# 09-I225-2.net
KiCad netlist of a schematic drawn in Altium Designer
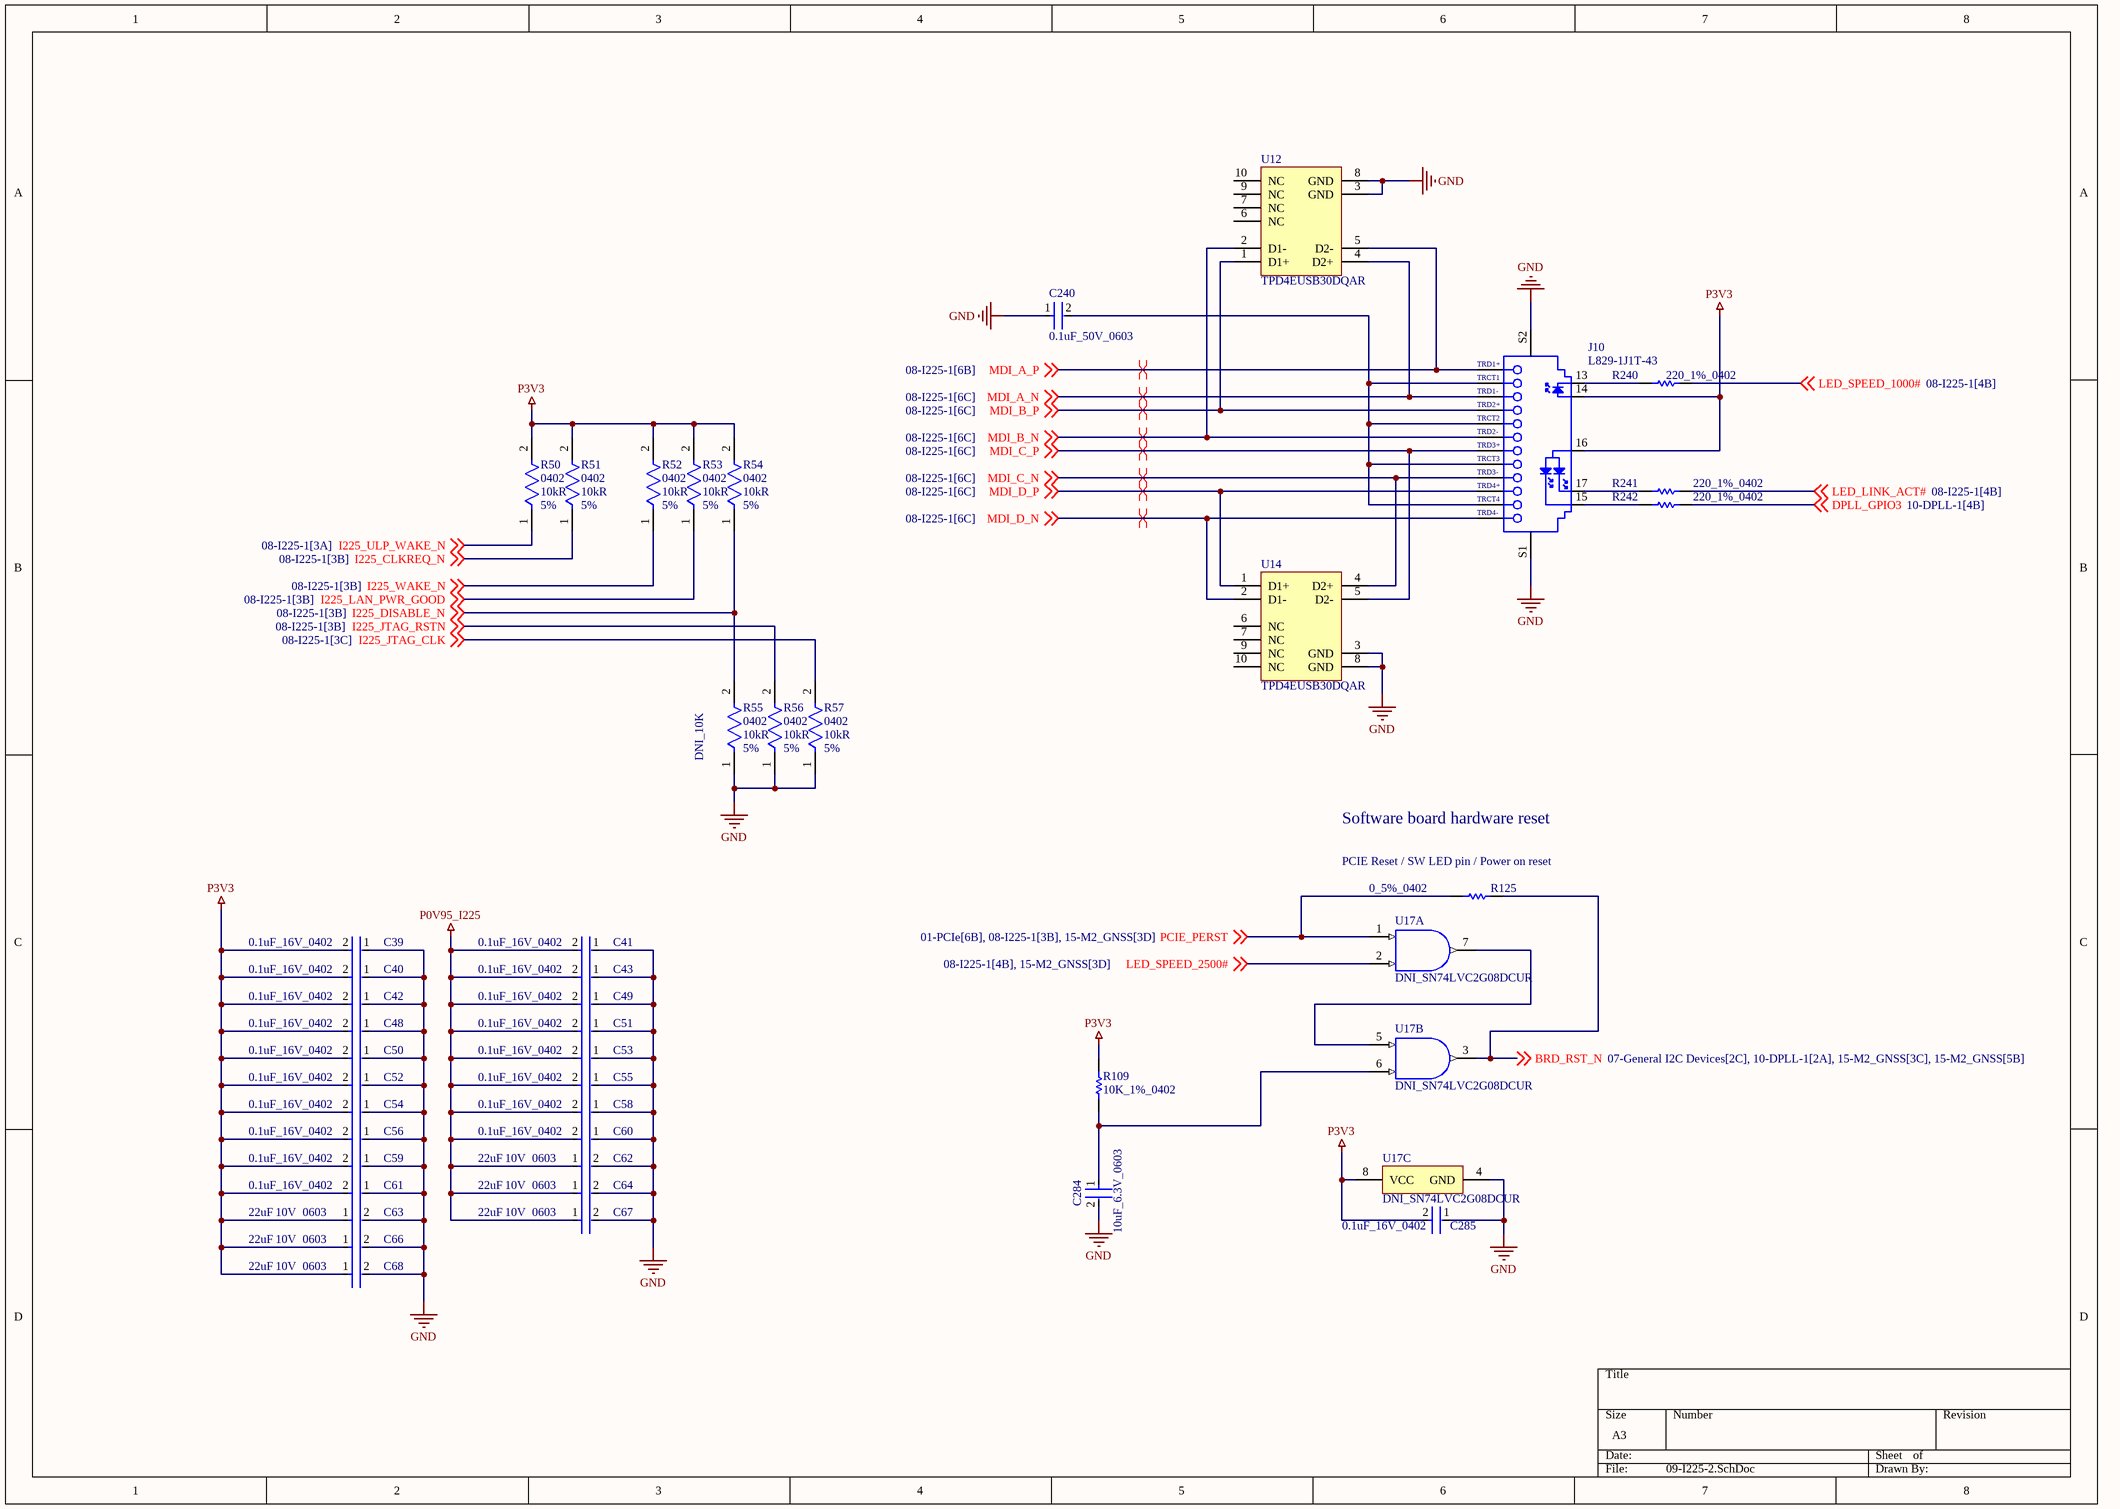
[diagram p0: 09-I225-2.SchDoc]

(export (version "E")
  (design (tool "Eeschema 10.0.6"))
  (components
    (comp (ref "C39")
      (value "0.1uF_16V_0402")
      (footprint "FP-GRM15-MFG")
      (description "CAP CER 0.1UF 16V X7R 0402")
      (fields (field (name "MANUFACTURER PART NUMBER") "GRM155R71C104KA88D") (field (name "TOLERANCE") "10%"))
      (libsource (lib "Altium Content Vault") (part "236180d848d6139a670b325ea6854c9"))
    )
    (comp (ref "C40")
      (value "0.1uF_16V_0402")
      (footprint "FP-GRM15-MFG")
      (description "CAP CER 0.1UF 16V X7R 0402")
      (fields (field (name "MANUFACTURER PART NUMBER") "GRM155R71C104KA88D") (field (name "TOLERANCE") "10%"))
      (libsource (lib "Altium Content Vault") (part "236180d848d6139a670b325ea6854c9"))
    )
    (comp (ref "C41")
      (value "0.1uF_16V_0402")
      (footprint "FP-GRM15-MFG")
      (description "CAP CER 0.1UF 16V X7R 0402")
      (fields (field (name "MANUFACTURER PART NUMBER") "GRM155R71C104KA88D") (field (name "TOLERANCE") "10%"))
      (libsource (lib "Altium Content Vault") (part "236180d848d6139a670b325ea6854c9"))
    )
    (comp (ref "C42")
      (value "0.1uF_16V_0402")
      (footprint "FP-GRM15-MFG")
      (description "CAP CER 0.1UF 16V X7R 0402")
      (fields (field (name "MANUFACTURER PART NUMBER") "GRM155R71C104KA88D") (field (name "TOLERANCE") "10%"))
      (libsource (lib "Altium Content Vault") (part "236180d848d6139a670b325ea6854c9"))
    )
    (comp (ref "C43")
      (value "0.1uF_16V_0402")
      (footprint "FP-GRM15-MFG")
      (description "CAP CER 0.1UF 16V X7R 0402")
      (fields (field (name "MANUFACTURER PART NUMBER") "GRM155R71C104KA88D") (field (name "TOLERANCE") "10%"))
      (libsource (lib "Altium Content Vault") (part "236180d848d6139a670b325ea6854c9"))
    )
    (comp (ref "C48")
      (value "0.1uF_16V_0402")
      (footprint "FP-GRM15-MFG")
      (description "CAP CER 0.1UF 16V X7R 0402")
      (fields (field (name "MANUFACTURER PART NUMBER") "GRM155R71C104KA88D") (field (name "TOLERANCE") "10%"))
      (libsource (lib "Altium Content Vault") (part "236180d848d6139a670b325ea6854c9"))
    )
    (comp (ref "C49")
      (value "0.1uF_16V_0402")
      (footprint "FP-GRM15-MFG")
      (description "CAP CER 0.1UF 16V X7R 0402")
      (fields (field (name "MANUFACTURER PART NUMBER") "GRM155R71C104KA88D") (field (name "TOLERANCE") "10%"))
      (libsource (lib "Altium Content Vault") (part "236180d848d6139a670b325ea6854c9"))
    )
    (comp (ref "C50")
      (value "0.1uF_16V_0402")
      (footprint "FP-GRM15-MFG")
      (description "CAP CER 0.1UF 16V X7R 0402")
      (fields (field (name "MANUFACTURER PART NUMBER") "GRM155R71C104KA88D") (field (name "TOLERANCE") "10%"))
      (libsource (lib "Altium Content Vault") (part "236180d848d6139a670b325ea6854c9"))
    )
    (comp (ref "C51")
      (value "0.1uF_16V_0402")
      (footprint "FP-GRM15-MFG")
      (description "CAP CER 0.1UF 16V X7R 0402")
      (fields (field (name "MANUFACTURER PART NUMBER") "GRM155R71C104KA88D") (field (name "TOLERANCE") "10%"))
      (libsource (lib "Altium Content Vault") (part "236180d848d6139a670b325ea6854c9"))
    )
    (comp (ref "C52")
      (value "0.1uF_16V_0402")
      (footprint "FP-GRM15-MFG")
      (description "CAP CER 0.1UF 16V X7R 0402")
      (fields (field (name "MANUFACTURER PART NUMBER") "GRM155R71C104KA88D") (field (name "TOLERANCE") "10%"))
      (libsource (lib "Altium Content Vault") (part "236180d848d6139a670b325ea6854c9"))
    )
    (comp (ref "C53")
      (value "0.1uF_16V_0402")
      (footprint "FP-GRM15-MFG")
      (description "CAP CER 0.1UF 16V X7R 0402")
      (fields (field (name "MANUFACTURER PART NUMBER") "GRM155R71C104KA88D") (field (name "TOLERANCE") "10%"))
      (libsource (lib "Altium Content Vault") (part "236180d848d6139a670b325ea6854c9"))
    )
    (comp (ref "C54")
      (value "0.1uF_16V_0402")
      (footprint "FP-GRM15-MFG")
      (description "CAP CER 0.1UF 16V X7R 0402")
      (fields (field (name "MANUFACTURER PART NUMBER") "GRM155R71C104KA88D") (field (name "TOLERANCE") "10%"))
      (libsource (lib "Altium Content Vault") (part "236180d848d6139a670b325ea6854c9"))
    )
    (comp (ref "C55")
      (value "0.1uF_16V_0402")
      (footprint "FP-GRM15-MFG")
      (description "CAP CER 0.1UF 16V X7R 0402")
      (fields (field (name "MANUFACTURER PART NUMBER") "GRM155R71C104KA88D") (field (name "TOLERANCE") "10%"))
      (libsource (lib "Altium Content Vault") (part "236180d848d6139a670b325ea6854c9"))
    )
    (comp (ref "C56")
      (value "0.1uF_16V_0402")
      (footprint "FP-GRM15-MFG")
      (description "CAP CER 0.1UF 16V X7R 0402")
      (fields (field (name "MANUFACTURER PART NUMBER") "GRM155R71C104KA88D") (field (name "TOLERANCE") "10%"))
      (libsource (lib "Altium Content Vault") (part "236180d848d6139a670b325ea6854c9"))
    )
    (comp (ref "C58")
      (value "0.1uF_16V_0402")
      (footprint "FP-GRM15-MFG")
      (description "CAP CER 0.1UF 16V X7R 0402")
      (fields (field (name "MANUFACTURER PART NUMBER") "GRM155R71C104KA88D") (field (name "TOLERANCE") "10%"))
      (libsource (lib "Altium Content Vault") (part "236180d848d6139a670b325ea6854c9"))
    )
    (comp (ref "C59")
      (value "0.1uF_16V_0402")
      (footprint "FP-GRM15-MFG")
      (description "CAP CER 0.1UF 16V X7R 0402")
      (fields (field (name "MANUFACTURER PART NUMBER") "GRM155R71C104KA88D") (field (name "TOLERANCE") "10%"))
      (libsource (lib "Altium Content Vault") (part "236180d848d6139a670b325ea6854c9"))
    )
    (comp (ref "C60")
      (value "0.1uF_16V_0402")
      (footprint "FP-GRM15-MFG")
      (description "CAP CER 0.1UF 16V X7R 0402")
      (fields (field (name "MANUFACTURER PART NUMBER") "GRM155R71C104KA88D") (field (name "TOLERANCE") "10%"))
      (libsource (lib "Altium Content Vault") (part "236180d848d6139a670b325ea6854c9"))
    )
    (comp (ref "C61")
      (value "0.1uF_16V_0402")
      (footprint "FP-GRM15-MFG")
      (description "CAP CER 0.1UF 16V X7R 0402")
      (fields (field (name "MANUFACTURER PART NUMBER") "GRM155R71C104KA88D") (field (name "TOLERANCE") "10%"))
      (libsource (lib "Altium Content Vault") (part "236180d848d6139a670b325ea6854c9"))
    )
    (comp (ref "C62")
      (value "GRM188R61A226ME15D")
      (footprint "FP-GRM188-0_2-IPC_C")
      (description "Chip Multilayer Ceramic Capacitors for General Purpose, 0603, 22uF, X5R, 15%, 20%, 10V")
      (fields
        (field (name "TOLERANCE") "20%")
        (field (name "CAPACITANCE") "22uF")
        (field (name "VOLTAGE RATING") "10V")
        (field (name "CASE CODE (IMPERIAL)") "0603")
      )
      (libsource (lib "Altium Content Vault") (part "11868f565c42a9108669ba33697ecf6"))
    )
    (comp (ref "C63")
      (value "GRM188R61A226ME15D")
      (footprint "FP-GRM188-0_2-IPC_C")
      (description "Chip Multilayer Ceramic Capacitors for General Purpose, 0603, 22uF, X5R, 15%, 20%, 10V")
      (fields
        (field (name "TOLERANCE") "20%")
        (field (name "CAPACITANCE") "22uF")
        (field (name "VOLTAGE RATING") "10V")
        (field (name "CASE CODE (IMPERIAL)") "0603")
      )
      (libsource (lib "Altium Content Vault") (part "11868f565c42a9108669ba33697ecf6"))
    )
    (comp (ref "C64")
      (value "GRM188R61A226ME15D")
      (footprint "FP-GRM188-0_2-IPC_C")
      (description "Chip Multilayer Ceramic Capacitors for General Purpose, 0603, 22uF, X5R, 15%, 20%, 10V")
      (fields
        (field (name "TOLERANCE") "20%")
        (field (name "CAPACITANCE") "22uF")
        (field (name "VOLTAGE RATING") "10V")
        (field (name "CASE CODE (IMPERIAL)") "0603")
      )
      (libsource (lib "Altium Content Vault") (part "11868f565c42a9108669ba33697ecf6"))
    )
    (comp (ref "C66")
      (value "GRM188R61A226ME15D")
      (footprint "FP-GRM188-0_2-IPC_C")
      (description "Chip Multilayer Ceramic Capacitors for General Purpose, 0603, 22uF, X5R, 15%, 20%, 10V")
      (fields
        (field (name "TOLERANCE") "20%")
        (field (name "CAPACITANCE") "22uF")
        (field (name "VOLTAGE RATING") "10V")
        (field (name "CASE CODE (IMPERIAL)") "0603")
      )
      (libsource (lib "Altium Content Vault") (part "11868f565c42a9108669ba33697ecf6"))
    )
    (comp (ref "C67")
      (value "GRM188R61A226ME15D")
      (footprint "FP-GRM188-0_2-IPC_C")
      (description "Chip Multilayer Ceramic Capacitors for General Purpose, 0603, 22uF, X5R, 15%, 20%, 10V")
      (fields
        (field (name "TOLERANCE") "20%")
        (field (name "CAPACITANCE") "22uF")
        (field (name "VOLTAGE RATING") "10V")
        (field (name "CASE CODE (IMPERIAL)") "0603")
      )
      (libsource (lib "Altium Content Vault") (part "11868f565c42a9108669ba33697ecf6"))
    )
    (comp (ref "C68")
      (value "GRM188R61A226ME15D")
      (footprint "FP-GRM188-0_2-IPC_C")
      (description "Chip Multilayer Ceramic Capacitors for General Purpose, 0603, 22uF, X5R, 15%, 20%, 10V")
      (fields
        (field (name "TOLERANCE") "20%")
        (field (name "CAPACITANCE") "22uF")
        (field (name "VOLTAGE RATING") "10V")
        (field (name "CASE CODE (IMPERIAL)") "0603")
      )
      (libsource (lib "Altium Content Vault") (part "11868f565c42a9108669ba33697ecf6"))
    )
    (comp (ref "C240")
      (value "0.1uF_50V_0603")
      (footprint "FP-C0603-CJ-MFG")
      (description "CAP CER 0.1UF 50V X7R 0603")
      (fields (field (name "MANUFACTURER PART NUMBER") "C0603X104K5RACTU") (field (name "VOLTAGE") "50V"))
      (libsource (lib "Altium Content Vault") (part "11868f565c42a9108669ba33697ecf6"))
    )
    (comp (ref "C284")
      (value "10uF_6.3V_0603")
      (footprint "FP-C0603C106M9PACTU-MFG")
      (description "CAP CER 10UF 6.3V X5R 0603")
      (fields
        (field (name "MANUFACTURER PART NUMBER") "C0603C106M9PACTU")
        (field (name "MANUFACTURER") "Kemet")
      )
      (libsource (lib "Altium Content Vault") (part "b4654b650e69147ec39a6b967a45e02"))
    )
    (comp (ref "C285")
      (value "0.1uF_16V_0402")
      (footprint "FP-GRM15-MFG")
      (description "CAP CER 0.1UF 16V X7R 0402")
      (fields (field (name "MANUFACTURER PART NUMBER") "GRM155R71C104KA88D") (field (name "TOLERANCE") "10%"))
      (libsource (lib "Altium Content Vault") (part "236180d848d6139a670b325ea6854c9"))
    )
    (comp (ref "J10")
      (value "L829-1J1T-43")
      (footprint "BELS-L829-1J1T-43_V")
      (description "Gigabit MagJack(R) Ultra Low Profile, 10/100/1000 Base-T, 19-Pin THD, RoHS, Tray")
      (libsource (lib "Altium Content Vault") (part "RJ45-17-2SHLD"))
    )
    (comp (ref "R50")
      (value "CRCW040210K0JNED")
      (footprint "FP-CRCW0402-e3-IPC_B")
      (description "RES Thick Film, 10kΩ, 5%, 0.063W, 200ppm/°C, 0402")
      (fields
        (field (name "CASE/PACKAGE") "0402")
        (field (name "RESISTANCE") "10kR")
        (field (name "TOLERANCE") "5%")
      )
      (libsource (lib "Altium Content Vault") (part "1029c3af85768c4190bb7ad29bc67b5"))
    )
    (comp (ref "R51")
      (value "CRCW040210K0JNED")
      (footprint "FP-CRCW0402-e3-IPC_B")
      (description "RES Thick Film, 10kΩ, 5%, 0.063W, 200ppm/°C, 0402")
      (fields
        (field (name "CASE/PACKAGE") "0402")
        (field (name "RESISTANCE") "10kR")
        (field (name "TOLERANCE") "5%")
      )
      (libsource (lib "Altium Content Vault") (part "1029c3af85768c4190bb7ad29bc67b5"))
    )
    (comp (ref "R52")
      (value "CRCW040210K0JNED")
      (footprint "FP-CRCW0402-e3-IPC_B")
      (description "RES Thick Film, 10kΩ, 5%, 0.063W, 200ppm/°C, 0402")
      (fields
        (field (name "CASE/PACKAGE") "0402")
        (field (name "RESISTANCE") "10kR")
        (field (name "TOLERANCE") "5%")
      )
      (libsource (lib "Altium Content Vault") (part "1029c3af85768c4190bb7ad29bc67b5"))
    )
    (comp (ref "R53")
      (value "CRCW040210K0JNED")
      (footprint "FP-CRCW0402-e3-IPC_B")
      (description "RES Thick Film, 10kΩ, 5%, 0.063W, 200ppm/°C, 0402")
      (fields
        (field (name "CASE/PACKAGE") "0402")
        (field (name "RESISTANCE") "10kR")
        (field (name "TOLERANCE") "5%")
      )
      (libsource (lib "Altium Content Vault") (part "1029c3af85768c4190bb7ad29bc67b5"))
    )
    (comp (ref "R54")
      (value "CRCW040210K0JNED")
      (footprint "FP-CRCW0402-e3-IPC_B")
      (description "RES Thick Film, 10kΩ, 5%, 0.063W, 200ppm/°C, 0402")
      (fields
        (field (name "CASE/PACKAGE") "0402")
        (field (name "RESISTANCE") "10kR")
        (field (name "TOLERANCE") "5%")
      )
      (libsource (lib "Altium Content Vault") (part "1029c3af85768c4190bb7ad29bc67b5"))
    )
    (comp (ref "R55")
      (value "DNI_10K")
      (footprint "FP-CRCW0402-e3-IPC_B")
      (description "RES Thick Film, 10kΩ, 5%, 0.063W, 200ppm/°C, 0402")
      (fields
        (field (name "CASE/PACKAGE") "0402")
        (field (name "RESISTANCE") "10kR")
        (field (name "TOLERANCE") "5%")
      )
      (libsource (lib "Altium Content Vault") (part "1029c3af85768c4190bb7ad29bc67b5"))
    )
    (comp (ref "R56")
      (value "CRCW040210K0JNED")
      (footprint "FP-CRCW0402-e3-IPC_B")
      (description "RES Thick Film, 10kΩ, 5%, 0.063W, 200ppm/°C, 0402")
      (fields
        (field (name "CASE/PACKAGE") "0402")
        (field (name "RESISTANCE") "10kR")
        (field (name "TOLERANCE") "5%")
      )
      (libsource (lib "Altium Content Vault") (part "1029c3af85768c4190bb7ad29bc67b5"))
    )
    (comp (ref "R57")
      (value "CRCW040210K0JNED")
      (footprint "FP-CRCW0402-e3-IPC_B")
      (description "RES Thick Film, 10kΩ, 5%, 0.063W, 200ppm/°C, 0402")
      (fields
        (field (name "CASE/PACKAGE") "0402")
        (field (name "RESISTANCE") "10kR")
        (field (name "TOLERANCE") "5%")
      )
      (libsource (lib "Altium Content Vault") (part "1029c3af85768c4190bb7ad29bc67b5"))
    )
    (comp (ref "R109")
      (value "10K_1%_0402")
      (footprint "RESC1005X40X25NL10T10")
      (fields (field (name "MANUFACTURER") "Bourns") (field (name "PART NUMBER") "CR0402-FX-1002GLF"))
      (libsource (lib "Altium Content Vault") (part "RES"))
    )
    (comp (ref "R125")
      (value "0_5%_0402")
      (footprint "RESC1005X40X25LL10T10")
      (fields (field (name "MANUFACTURER") "KOA Speer") (field (name "PART NUMBER") "RK73Z1ETTP"))
      (libsource (lib "Altium Content Vault") (part "RES"))
    )
    (comp (ref "R240")
      (value "220_1%_0402")
      (footprint "RESC1005X40X25LL10T10")
      (fields (field (name "PART NUMBER") "RK73H1ETTP2200F") (field (name "MANUFACTURER") "KOA Speer"))
      (libsource (lib "Altium Content Vault") (part "RES"))
    )
    (comp (ref "R241")
      (value "220_1%_0402")
      (footprint "RESC1005X40X25LL10T10")
      (fields (field (name "PART NUMBER") "RK73H1ETTP2200F") (field (name "MANUFACTURER") "KOA Speer"))
      (libsource (lib "Altium Content Vault") (part "RES"))
    )
    (comp (ref "R242")
      (value "220_1%_0402")
      (footprint "RESC1005X40X25LL10T10")
      (fields (field (name "PART NUMBER") "RK73H1ETTP2200F") (field (name "MANUFACTURER") "KOA Speer"))
      (libsource (lib "Altium Content Vault") (part "RES"))
    )
    (comp (ref "U12")
      (value "TPD4EUSB30DQAR")
      (footprint "DQA0010A_V")
      (fields (field (name "MANUFACTURER") "Texas Instruments"))
      (libsource (lib "Altium Content Vault") (part "TI-TPD4EUSB30-SON_DQA-10"))
    )
    (comp (ref "U14")
      (value "TPD4EUSB30DQAR")
      (footprint "DQA0010A_V")
      (fields (field (name "MANUFACTURER") "Texas Instruments"))
      (libsource (lib "") (part "TI-TPD4EUSB30-SON_DQA-10_1"))
    )
    (comp (ref "U17")
      (value "DNI_SN74LVC2G08DCUR")
      (footprint "DCU0008A_M")
      (description "Dual 2-Input Positive-AND Gate, DCU0008A, LARGE T&R")
      (fields
        (field (name "MANUFACTURER") "Texas Instruments")
        (field (name "GENERIC PART NUMBER") "SN74LVC2G08")
      )
      (libsource (lib "Altium Content Vault") (part "TI-SN74XXX2G08-8"))
    )
  )
  (nets
    (net (code "1") (name "BRD_RST_N") (class "Default")
      (node (ref "R125") (pin "2") (pinfunction "2_2") (pintype "passive"))
      (node (ref "U17") (pin "3") (pinfunction "2Y_3") (pintype "output"))
    )
    (net (code "2") (name "DPLL_GPIO3") (class "Default")
      (node (ref "R242") (pin "2") (pinfunction "2_2") (pintype "passive"))
    )
    (net (code "3") (name "GND") (class "Default")
      (node (ref "C240") (pin "1") (pinfunction "1_1") (pintype "passive"))
      (node (ref "C284") (pin "2") (pinfunction "2_2") (pintype "passive"))
      (node (ref "C285") (pin "1") (pinfunction "1_1") (pintype "passive"))
      (node (ref "C39") (pin "1") (pinfunction "1_1") (pintype "passive"))
      (node (ref "C40") (pin "1") (pinfunction "1_1") (pintype "passive"))
      (node (ref "C41") (pin "1") (pinfunction "1_1") (pintype "passive"))
      (node (ref "C42") (pin "1") (pinfunction "1_1") (pintype "passive"))
      (node (ref "C43") (pin "1") (pinfunction "1_1") (pintype "passive"))
      (node (ref "C48") (pin "1") (pinfunction "1_1") (pintype "passive"))
      (node (ref "C49") (pin "1") (pinfunction "1_1") (pintype "passive"))
      (node (ref "C50") (pin "1") (pinfunction "1_1") (pintype "passive"))
      (node (ref "C51") (pin "1") (pinfunction "1_1") (pintype "passive"))
      (node (ref "C52") (pin "1") (pinfunction "1_1") (pintype "passive"))
      (node (ref "C53") (pin "1") (pinfunction "1_1") (pintype "passive"))
      (node (ref "C54") (pin "1") (pinfunction "1_1") (pintype "passive"))
      (node (ref "C55") (pin "1") (pinfunction "1_1") (pintype "passive"))
      (node (ref "C56") (pin "1") (pinfunction "1_1") (pintype "passive"))
      (node (ref "C58") (pin "1") (pinfunction "1_1") (pintype "passive"))
      (node (ref "C59") (pin "1") (pinfunction "1_1") (pintype "passive"))
      (node (ref "C60") (pin "1") (pinfunction "1_1") (pintype "passive"))
      (node (ref "C61") (pin "1") (pinfunction "1_1") (pintype "passive"))
      (node (ref "C62") (pin "2") (pinfunction "2_2") (pintype "passive"))
      (node (ref "C63") (pin "2") (pinfunction "2_2") (pintype "passive"))
      (node (ref "C64") (pin "2") (pinfunction "2_2") (pintype "passive"))
      (node (ref "C66") (pin "2") (pinfunction "2_2") (pintype "passive"))
      (node (ref "C67") (pin "2") (pinfunction "2_2") (pintype "passive"))
      (node (ref "C68") (pin "2") (pinfunction "2_2") (pintype "passive"))
      (node (ref "J10") (pin "S1") (pinfunction "S1_S1") (pintype "passive"))
      (node (ref "J10") (pin "S2") (pinfunction "S2_S2") (pintype "passive"))
      (node (ref "R55") (pin "1") (pinfunction "1_1") (pintype "passive"))
      (node (ref "R56") (pin "1") (pinfunction "1_1") (pintype "passive"))
      (node (ref "R57") (pin "1") (pinfunction "1_1") (pintype "passive"))
      (node (ref "U12") (pin "3") (pinfunction "GND_3") (pintype "power_in"))
      (node (ref "U12") (pin "8") (pinfunction "GND_8") (pintype "power_in"))
      (node (ref "U14") (pin "3") (pinfunction "GND_3") (pintype "power_in"))
      (node (ref "U14") (pin "8") (pinfunction "GND_8") (pintype "power_in"))
      (node (ref "U17") (pin "4") (pinfunction "GND_4") (pintype "power_in"))
    )
    (net (code "4") (name "I225_CLKREQ_N") (class "Default")
      (node (ref "R51") (pin "1") (pinfunction "1_1") (pintype "passive"))
    )
    (net (code "5") (name "I225_DISABLE_N") (class "Default")
      (node (ref "R54") (pin "1") (pinfunction "1_1") (pintype "passive"))
      (node (ref "R55") (pin "2") (pinfunction "2_2") (pintype "passive"))
    )
    (net (code "6") (name "I225_JTAG_CLK") (class "Default")
      (node (ref "R57") (pin "2") (pinfunction "2_2") (pintype "passive"))
    )
    (net (code "7") (name "I225_JTAG_RSTN") (class "Default")
      (node (ref "R56") (pin "2") (pinfunction "2_2") (pintype "passive"))
    )
    (net (code "8") (name "I225_LAN_PWR_GOOD") (class "Default")
      (node (ref "R53") (pin "1") (pinfunction "1_1") (pintype "passive"))
    )
    (net (code "9") (name "I225_ULP_WAKE_N") (class "Default")
      (node (ref "R50") (pin "1") (pinfunction "1_1") (pintype "passive"))
    )
    (net (code "10") (name "I225_WAKE_N") (class "Default")
      (node (ref "R52") (pin "1") (pinfunction "1_1") (pintype "passive"))
    )
    (net (code "11") (name "LED_LINK_ACT#") (class "Default")
      (node (ref "R241") (pin "2") (pinfunction "2_2") (pintype "passive"))
    )
    (net (code "12") (name "LED_SPEED_1000#") (class "Default")
      (node (ref "R240") (pin "2") (pinfunction "2_2") (pintype "passive"))
    )
    (net (code "13") (name "LED_SPEED_2500#") (class "Default")
      (node (ref "U17") (pin "2") (pinfunction "1B_2") (pintype "input"))
    )
    (net (code "14") (name "MDI_A_N") (class "Default")
      (node (ref "J10") (pin "3") (pinfunction "TRD1-_3") (pintype "passive"))
      (node (ref "U12") (pin "4") (pinfunction "D2+_4") (pintype "passive"))
    )
    (net (code "15") (name "MDI_A_P") (class "Default")
      (node (ref "J10") (pin "1") (pinfunction "TRD1+_1") (pintype "passive"))
      (node (ref "U12") (pin "5") (pinfunction "D2-_5") (pintype "passive"))
    )
    (net (code "16") (name "MDI_B_N") (class "Default")
      (node (ref "J10") (pin "6") (pinfunction "TRD2-_6") (pintype "passive"))
      (node (ref "U12") (pin "2") (pinfunction "D1-_2") (pintype "passive"))
    )
    (net (code "17") (name "MDI_B_P") (class "Default")
      (node (ref "J10") (pin "4") (pinfunction "TRD2+_4") (pintype "passive"))
      (node (ref "U12") (pin "1") (pinfunction "D1+_1") (pintype "passive"))
    )
    (net (code "18") (name "MDI_C_N") (class "Default")
      (node (ref "J10") (pin "9") (pinfunction "TRD3-_9") (pintype "passive"))
      (node (ref "U14") (pin "4") (pinfunction "D2+_4") (pintype "passive"))
    )
    (net (code "19") (name "MDI_C_P") (class "Default")
      (node (ref "J10") (pin "7") (pinfunction "TRD3+_7") (pintype "passive"))
      (node (ref "U14") (pin "5") (pinfunction "D2-_5") (pintype "passive"))
    )
    (net (code "20") (name "MDI_D_N") (class "Default")
      (node (ref "J10") (pin "12") (pinfunction "TRD4-_12") (pintype "passive"))
      (node (ref "U14") (pin "2") (pinfunction "D1-_2") (pintype "passive"))
    )
    (net (code "21") (name "MDI_D_P") (class "Default")
      (node (ref "J10") (pin "10") (pinfunction "TRD4+_10") (pintype "passive"))
      (node (ref "U14") (pin "1") (pinfunction "D1+_1") (pintype "passive"))
    )
    (net (code "22") (name "Net-(J10-Pad13)") (class "Default")
      (node (ref "J10") (pin "13") (pinfunction "13_13") (pintype "passive"))
      (node (ref "R240") (pin "1") (pinfunction "1_1") (pintype "passive"))
    )
    (net (code "23") (name "Net-(J10-Pad15)") (class "Default")
      (node (ref "J10") (pin "15") (pinfunction "15_15") (pintype "passive"))
      (node (ref "R242") (pin "1") (pinfunction "1_1") (pintype "passive"))
    )
    (net (code "24") (name "Net-(J10-Pad17)") (class "Default")
      (node (ref "J10") (pin "17") (pinfunction "17_17") (pintype "passive"))
      (node (ref "R241") (pin "1") (pinfunction "1_1") (pintype "passive"))
    )
    (net (code "25") (name "Net-(J10-TRCT1)") (class "Default")
      (node (ref "C240") (pin "2") (pinfunction "2_2") (pintype "passive"))
      (node (ref "J10") (pin "11") (pinfunction "TRCT4_11") (pintype "passive"))
      (node (ref "J10") (pin "2") (pinfunction "TRCT1_2") (pintype "passive"))
      (node (ref "J10") (pin "5") (pinfunction "TRCT2_5") (pintype "passive"))
      (node (ref "J10") (pin "8") (pinfunction "TRCT3_8") (pintype "passive"))
    )
    (net (code "26") (name "Net-(U17A-1Y)") (class "Default")
      (node (ref "U17") (pin "5") (pinfunction "2A_5") (pintype "input"))
      (node (ref "U17") (pin "7") (pinfunction "1Y_7") (pintype "output"))
    )
    (net (code "27") (name "Net-(U17B-2B)") (class "Default")
      (node (ref "C284") (pin "1") (pinfunction "1_1") (pintype "passive"))
      (node (ref "R109") (pin "1") (pinfunction "1_1") (pintype "passive"))
      (node (ref "U17") (pin "6") (pinfunction "2B_6") (pintype "input"))
    )
    (net (code "28") (name "P0V95_I225") (class "Default")
      (node (ref "C41") (pin "2") (pinfunction "2_2") (pintype "passive"))
      (node (ref "C43") (pin "2") (pinfunction "2_2") (pintype "passive"))
      (node (ref "C49") (pin "2") (pinfunction "2_2") (pintype "passive"))
      (node (ref "C51") (pin "2") (pinfunction "2_2") (pintype "passive"))
      (node (ref "C53") (pin "2") (pinfunction "2_2") (pintype "passive"))
      (node (ref "C55") (pin "2") (pinfunction "2_2") (pintype "passive"))
      (node (ref "C58") (pin "2") (pinfunction "2_2") (pintype "passive"))
      (node (ref "C60") (pin "2") (pinfunction "2_2") (pintype "passive"))
      (node (ref "C62") (pin "1") (pinfunction "1_1") (pintype "passive"))
      (node (ref "C64") (pin "1") (pinfunction "1_1") (pintype "passive"))
      (node (ref "C67") (pin "1") (pinfunction "1_1") (pintype "passive"))
    )
    (net (code "29") (name "P3V3") (class "Default")
      (node (ref "C285") (pin "2") (pinfunction "2_2") (pintype "passive"))
      (node (ref "C39") (pin "2") (pinfunction "2_2") (pintype "passive"))
      (node (ref "C40") (pin "2") (pinfunction "2_2") (pintype "passive"))
      (node (ref "C42") (pin "2") (pinfunction "2_2") (pintype "passive"))
      (node (ref "C48") (pin "2") (pinfunction "2_2") (pintype "passive"))
      (node (ref "C50") (pin "2") (pinfunction "2_2") (pintype "passive"))
      (node (ref "C52") (pin "2") (pinfunction "2_2") (pintype "passive"))
      (node (ref "C54") (pin "2") (pinfunction "2_2") (pintype "passive"))
      (node (ref "C56") (pin "2") (pinfunction "2_2") (pintype "passive"))
      (node (ref "C59") (pin "2") (pinfunction "2_2") (pintype "passive"))
      (node (ref "C61") (pin "2") (pinfunction "2_2") (pintype "passive"))
      (node (ref "C63") (pin "1") (pinfunction "1_1") (pintype "passive"))
      (node (ref "C66") (pin "1") (pinfunction "1_1") (pintype "passive"))
      (node (ref "C68") (pin "1") (pinfunction "1_1") (pintype "passive"))
      (node (ref "J10") (pin "14") (pinfunction "14_14") (pintype "passive"))
      (node (ref "J10") (pin "16") (pinfunction "16_16") (pintype "passive"))
      (node (ref "R109") (pin "2") (pinfunction "2_2") (pintype "passive"))
      (node (ref "R50") (pin "2") (pinfunction "2_2") (pintype "passive"))
      (node (ref "R51") (pin "2") (pinfunction "2_2") (pintype "passive"))
      (node (ref "R52") (pin "2") (pinfunction "2_2") (pintype "passive"))
      (node (ref "R53") (pin "2") (pinfunction "2_2") (pintype "passive"))
      (node (ref "R54") (pin "2") (pinfunction "2_2") (pintype "passive"))
      (node (ref "U17") (pin "8") (pinfunction "VCC_8") (pintype "power_in"))
    )
    (net (code "30") (name "PCIE_PERST") (class "Default")
      (node (ref "R125") (pin "1") (pinfunction "1_1") (pintype "passive"))
      (node (ref "U17") (pin "1") (pinfunction "1A_1") (pintype "input"))
    )
    (net (code "31") (name "unconnected-(U12-NC-Pad6)") (class "Default")
      (node (ref "U12") (pin "6") (pinfunction "NC_6") (pintype "passive"))
    )
    (net (code "32") (name "unconnected-(U12-NC-Pad7)") (class "Default")
      (node (ref "U12") (pin "7") (pinfunction "NC_7") (pintype "passive"))
    )
    (net (code "33") (name "unconnected-(U12-NC-Pad9)") (class "Default")
      (node (ref "U12") (pin "9") (pinfunction "NC_9") (pintype "passive"))
    )
    (net (code "34") (name "unconnected-(U12-NC-Pad10)") (class "Default")
      (node (ref "U12") (pin "10") (pinfunction "NC_10") (pintype "passive"))
    )
    (net (code "35") (name "unconnected-(U14-NC-Pad6)") (class "Default")
      (node (ref "U14") (pin "6") (pinfunction "NC_6") (pintype "passive"))
    )
    (net (code "36") (name "unconnected-(U14-NC-Pad7)") (class "Default")
      (node (ref "U14") (pin "7") (pinfunction "NC_7") (pintype "passive"))
    )
    (net (code "37") (name "unconnected-(U14-NC-Pad9)") (class "Default")
      (node (ref "U14") (pin "9") (pinfunction "NC_9") (pintype "passive"))
    )
    (net (code "38") (name "unconnected-(U14-NC-Pad10)") (class "Default")
      (node (ref "U14") (pin "10") (pinfunction "NC_10") (pintype "passive"))
    )
  )
)
